# 12V_to_5V_LDO_1A.net
KiCad netlist of a schematic drawn in Altium Designer
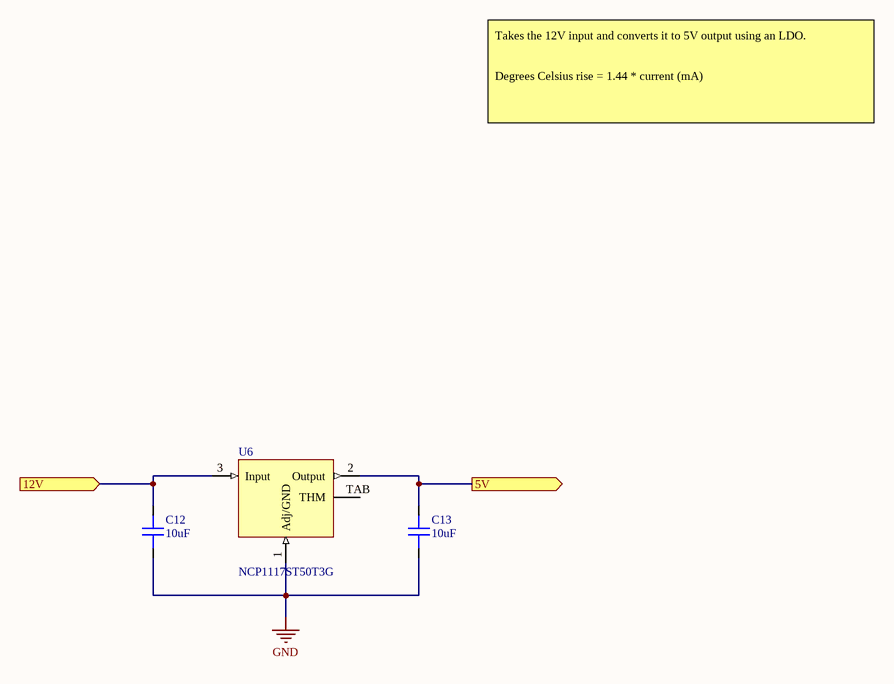
[diagram p0: 12V_to_5V_LDO_1A.SchDoc]

(export (version "E")
  (design (tool "Eeschema 10.0.6"))
  (components
    (comp (ref "C12")
      (value "capacitor")
      (footprint "0603")
      (description "Generic 0603 capacitor")
      (fields (field (name "CAPACITANCE") "10uF") (field (name "VOLTAGE") "50"))
      (libsource (lib "altlib") (part "capacitor"))
    )
    (comp (ref "C13")
      (value "capacitor")
      (footprint "0603")
      (description "Generic 0603 capacitor")
      (fields (field (name "CAPACITANCE") "10uF") (field (name "VOLTAGE") "50"))
      (libsource (lib "altlib") (part "capacitor"))
    )
    (comp (ref "U6")
      (value "NCP1117ST50T3G")
      (footprint "SOT-223-3")
      (description "5V linear regulator")
      (libsource (lib "altlib") (part "NCP1117ST50T3G"))
    )
  )
  (nets
    (net (code "1") (name "/5V") (class "Default")
      (node (ref "C13") (pin "2") (pinfunction "2_2") (pintype "passive"))
      (node (ref "U6") (pin "2") (pinfunction "Output_2") (pintype "output"))
    )
    (net (code "2") (name "/12V") (class "Default")
      (node (ref "C12") (pin "2") (pinfunction "2_2") (pintype "passive"))
      (node (ref "U6") (pin "3") (pinfunction "Input_3") (pintype "input"))
    )
    (net (code "3") (name "GND") (class "Default")
      (node (ref "C12") (pin "1") (pinfunction "1_1") (pintype "passive"))
      (node (ref "C13") (pin "1") (pinfunction "1_1") (pintype "passive"))
      (node (ref "U6") (pin "1") (pinfunction "Adj/GND_1") (pintype "input"))
    )
    (net (code "4") (name "unconnected-(U6-THM-PadTAB)") (class "Default")
      (node (ref "U6") (pin "TAB") (pinfunction "THM_TAB") (pintype "passive"))
    )
  )
)
